# SCH-1-Relay_circuit.net
KiCad netlist of a schematic drawn in Altium Designer
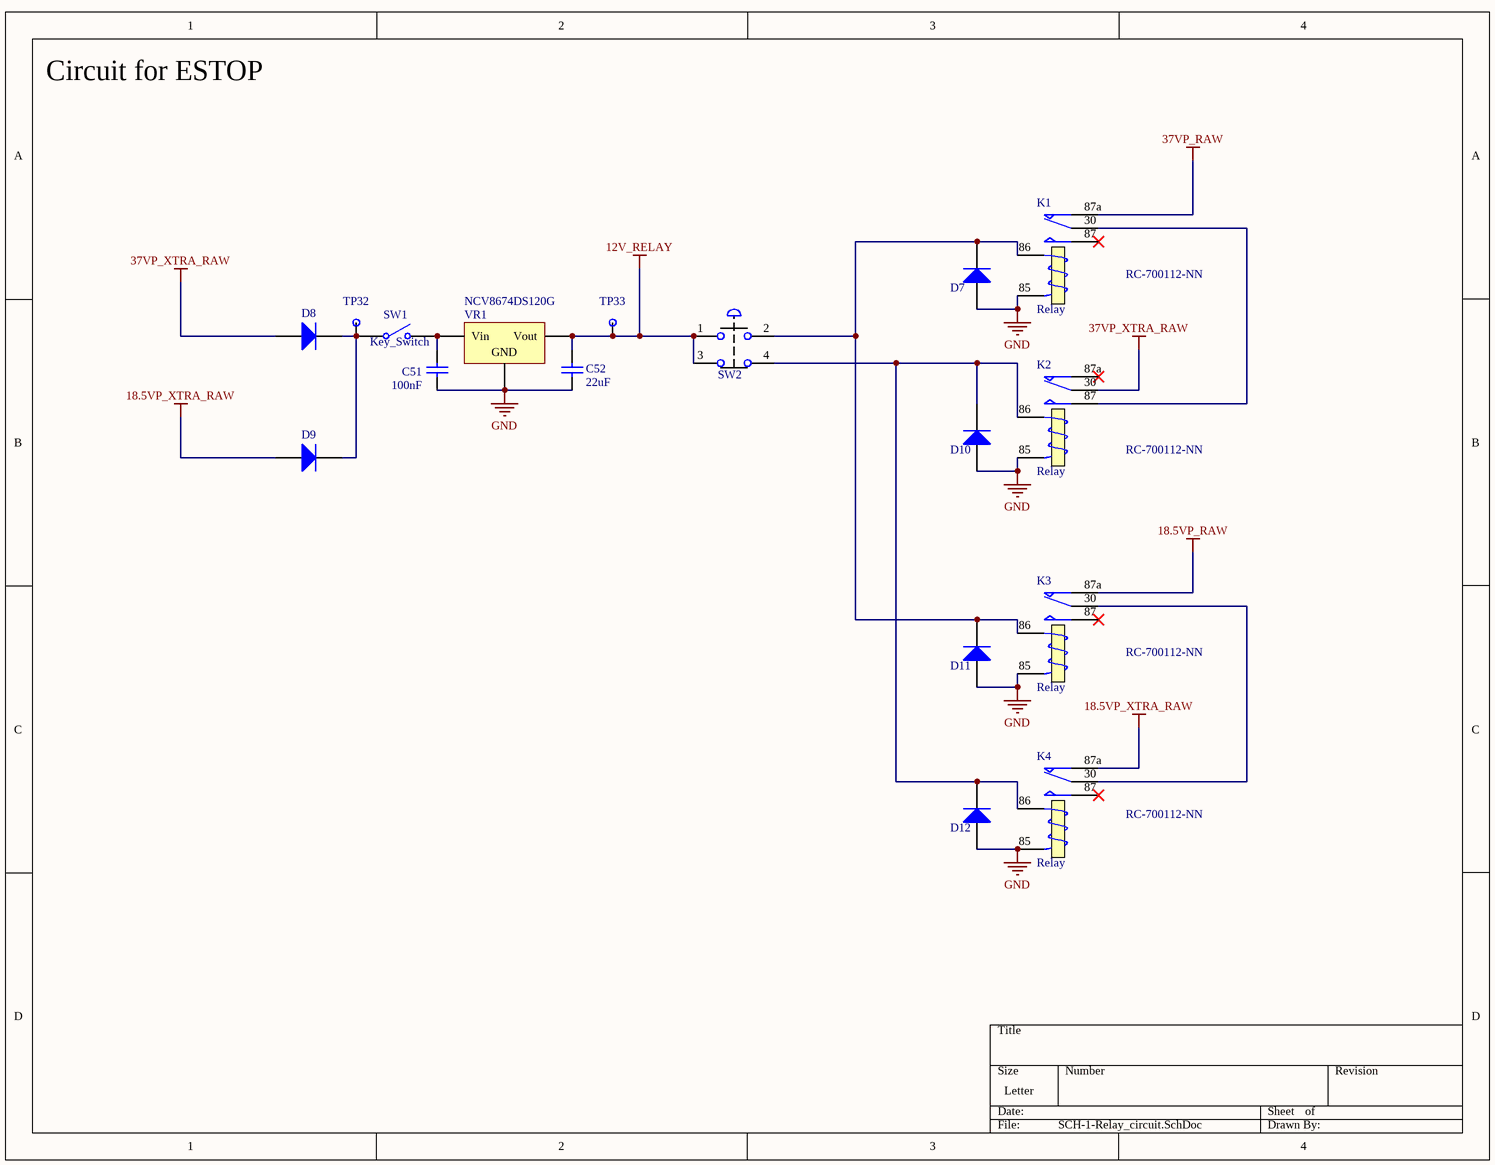
[diagram p0: SCH-1-Relay_circuit.SchDoc]

(export (version "E")
  (design (tool "Eeschema 10.0.6"))
  (components
    (comp (ref "C51")
      (value "100nF")
      (footprint "1608[0603]")
      (description "Capacitor")
      (fields (field (name "Comment") "Cap") (field (name "PUBLISHER") "Altium Limited"))
      (libsource (lib "Miscellaneous Devices") (part "Cap"))
    )
    (comp (ref "C52")
      (value "22uF")
      (footprint "1608[0603]")
      (description "Capacitor")
      (fields (field (name "Comment") "Cap") (field (name "PUBLISHER") "Altium Limited"))
      (libsource (lib "Miscellaneous Devices") (part "Cap"))
    )
    (comp (ref "D7")
      (value "Diode 1N4001")
      (footprint "DO-41")
      (description "1 Amp General Purpose Rectifier")
      (fields (field (name "PUBLISHER") "Altium Limited"))
      (libsource (lib "Miscellaneous Devices") (part "Diode 1N4001"))
    )
    (comp (ref "D8")
      (value "Diode 1N4001")
      (footprint "DO-41")
      (description "1 Amp General Purpose Rectifier")
      (fields (field (name "PUBLISHER") "Altium Limited"))
      (libsource (lib "Miscellaneous Devices") (part "Diode 1N4001"))
    )
    (comp (ref "D9")
      (value "Diode 1N4001")
      (footprint "DO-41")
      (description "1 Amp General Purpose Rectifier")
      (fields (field (name "PUBLISHER") "Altium Limited"))
      (libsource (lib "Miscellaneous Devices") (part "Diode 1N4001"))
    )
    (comp (ref "D10")
      (value "Diode 1N4001")
      (footprint "DO-41")
      (description "1 Amp General Purpose Rectifier")
      (fields (field (name "PUBLISHER") "Altium Limited"))
      (libsource (lib "Miscellaneous Devices") (part "Diode 1N4001"))
    )
    (comp (ref "D11")
      (value "Diode 1N4001")
      (footprint "DO-41")
      (description "1 Amp General Purpose Rectifier")
      (fields (field (name "PUBLISHER") "Altium Limited"))
      (libsource (lib "Miscellaneous Devices") (part "Diode 1N4001"))
    )
    (comp (ref "D12")
      (value "Diode 1N4001")
      (footprint "DO-41")
      (description "1 Amp General Purpose Rectifier")
      (fields (field (name "PUBLISHER") "Altium Limited"))
      (libsource (lib "Miscellaneous Devices") (part "Diode 1N4001"))
    )
    (comp (ref "K1")
      (value "Relay")
      (footprint "Relay RC-700112-NN")
      (description "SPDT Relay")
      (fields (field (name "PUBLISHER") "Altium Limited"))
      (libsource (lib "RSX_Relays") (part "Relay"))
    )
    (comp (ref "K2")
      (value "Relay")
      (footprint "Relay RC-700112-NN")
      (description "SPDT Relay")
      (fields (field (name "PUBLISHER") "Altium Limited"))
      (libsource (lib "RSX_Relays") (part "Relay"))
    )
    (comp (ref "K3")
      (value "Relay")
      (footprint "Relay RC-700112-NN")
      (description "SPDT Relay")
      (fields (field (name "PUBLISHER") "Altium Limited"))
      (libsource (lib "RSX_Relays") (part "Relay"))
    )
    (comp (ref "K4")
      (value "Relay")
      (footprint "Relay RC-700112-NN")
      (description "SPDT Relay")
      (fields (field (name "PUBLISHER") "Altium Limited"))
      (libsource (lib "RSX_Relays") (part "Relay"))
    )
    (comp (ref "SW1")
      (value "Key_Switch")
      (footprint "MOLEX_0039293026")
      (fields (field (name "PUBLISHER") "Altium Limited"))
      (libsource (lib "RSX_Miscellaneous") (part "Key_Switch"))
    )
    (comp (ref "SW2")
      (value "NO-NC ESD with light")
      (footprint "MOLEX 0039281043")
      (libsource (lib "RSX_Miscellaneous") (part "DPST ESTOP"))
    )
    (comp (ref "TP32")
      (value "TestPt")
      (footprint "50_MIL_PAD")
      (libsource (lib "RSX_Test_Points") (part "TestPt"))
    )
    (comp (ref "TP33")
      (value "TestPt")
      (footprint "50_MIL_PAD")
      (libsource (lib "RSX_Test_Points") (part "TestPt"))
    )
    (comp (ref "VR1")
      (value "Volt Reg")
      (footprint "DPAK254P1420X457-3N")
      (description "Voltage Regulator")
      (fields (field (name "PUBLISHER") "Altium Limited"))
      (libsource (lib "RSX_ICs") (part "Volt Reg"))
    )
  )
  (nets
    (net (code "1") (name "12V_RELAY") (class "Default")
      (node (ref "C52") (pin "1") (pinfunction "1_1") (pintype "passive"))
      (node (ref "SW2") (pin "1") (pintype "passive"))
      (node (ref "SW2") (pin "3") (pintype "passive"))
      (node (ref "TP33") (pin "1") (pinfunction "1_1") (pintype "passive"))
      (node (ref "VR1") (pin "3") (pinfunction "Vout_3") (pintype "passive"))
    )
    (net (code "2") (name "18.5VP_RAW") (class "Default")
      (node (ref "K3") (pin "87a") (pinfunction "NC_87a") (pintype "passive"))
    )
    (net (code "3") (name "18.5VP_XTRA_RAW") (class "Default")
      (node (ref "D9") (pin "1") (pinfunction "A_1") (pintype "passive"))
      (node (ref "K4") (pin "87a") (pinfunction "NC_87a") (pintype "passive"))
    )
    (net (code "4") (name "37VP_RAW") (class "Default")
      (node (ref "K1") (pin "87a") (pinfunction "NC_87a") (pintype "passive"))
    )
    (net (code "5") (name "37VP_XTRA_RAW") (class "Default")
      (node (ref "D8") (pin "1") (pinfunction "A_1") (pintype "passive"))
      (node (ref "K2") (pin "30") (pinfunction "COM_30") (pintype "passive"))
    )
    (net (code "6") (name "GND") (class "Default")
      (node (ref "C51") (pin "2") (pinfunction "2_2") (pintype "passive"))
      (node (ref "C52") (pin "2") (pinfunction "2_2") (pintype "passive"))
      (node (ref "D10") (pin "1") (pinfunction "A_1") (pintype "passive"))
      (node (ref "D11") (pin "1") (pinfunction "A_1") (pintype "passive"))
      (node (ref "D12") (pin "1") (pinfunction "A_1") (pintype "passive"))
      (node (ref "D7") (pin "1") (pinfunction "A_1") (pintype "passive"))
      (node (ref "K1") (pin "85") (pinfunction "T2_85") (pintype "passive"))
      (node (ref "K2") (pin "85") (pinfunction "T2_85") (pintype "passive"))
      (node (ref "K3") (pin "85") (pinfunction "T2_85") (pintype "passive"))
      (node (ref "K4") (pin "85") (pinfunction "T2_85") (pintype "passive"))
      (node (ref "VR1") (pin "2") (pinfunction "GND_2") (pintype "passive"))
    )
    (net (code "7") (name "Net-(D8-K)") (class "Default")
      (node (ref "D8") (pin "2") (pinfunction "K_2") (pintype "passive"))
      (node (ref "D9") (pin "2") (pinfunction "K_2") (pintype "passive"))
      (node (ref "SW1") (pin "1") (pinfunction "COMMON_1") (pintype "passive"))
      (node (ref "TP32") (pin "1") (pinfunction "1_1") (pintype "passive"))
    )
    (net (code "8") (name "Net-(D10-K)") (class "Default")
      (node (ref "D10") (pin "2") (pinfunction "K_2") (pintype "passive"))
      (node (ref "D12") (pin "2") (pinfunction "K_2") (pintype "passive"))
      (node (ref "K2") (pin "86") (pinfunction "T1_86") (pintype "passive"))
      (node (ref "K4") (pin "86") (pinfunction "T1_86") (pintype "passive"))
      (node (ref "SW2") (pin "4") (pintype "passive"))
    )
    (net (code "9") (name "Net-(D11-K)") (class "Default")
      (node (ref "D11") (pin "2") (pinfunction "K_2") (pintype "passive"))
      (node (ref "D7") (pin "2") (pinfunction "K_2") (pintype "passive"))
      (node (ref "K1") (pin "86") (pinfunction "T1_86") (pintype "passive"))
      (node (ref "K3") (pin "86") (pinfunction "T1_86") (pintype "passive"))
      (node (ref "SW2") (pin "2") (pintype "passive"))
    )
    (net (code "10") (name "Net-(K1-COM)") (class "Default")
      (node (ref "K1") (pin "30") (pinfunction "COM_30") (pintype "passive"))
      (node (ref "K2") (pin "87") (pinfunction "NO_87") (pintype "passive"))
    )
    (net (code "11") (name "Net-(K3-COM)") (class "Default")
      (node (ref "K3") (pin "30") (pinfunction "COM_30") (pintype "passive"))
      (node (ref "K4") (pin "30") (pinfunction "COM_30") (pintype "passive"))
    )
    (net (code "12") (name "Net-(SW1-NO)") (class "Default")
      (node (ref "C51") (pin "1") (pinfunction "1_1") (pintype "passive"))
      (node (ref "SW1") (pin "2") (pinfunction "NO_2") (pintype "passive"))
      (node (ref "VR1") (pin "1") (pinfunction "Vin_1") (pintype "passive"))
    )
    (net (code "13") (name "unconnected-(K1-NO-Pad87)") (class "Default")
      (node (ref "K1") (pin "87") (pinfunction "NO_87") (pintype "passive+no_connect"))
    )
    (net (code "14") (name "unconnected-(K2-NC-Pad87a)") (class "Default")
      (node (ref "K2") (pin "87a") (pinfunction "NC_87a") (pintype "passive+no_connect"))
    )
    (net (code "15") (name "unconnected-(K3-NO-Pad87)") (class "Default")
      (node (ref "K3") (pin "87") (pinfunction "NO_87") (pintype "passive+no_connect"))
    )
    (net (code "16") (name "unconnected-(K4-NO-Pad87)") (class "Default")
      (node (ref "K4") (pin "87") (pinfunction "NO_87") (pintype "passive+no_connect"))
    )
  )
)
